# IRRemote.net
KiCad netlist of a schematic drawn in EAGLE
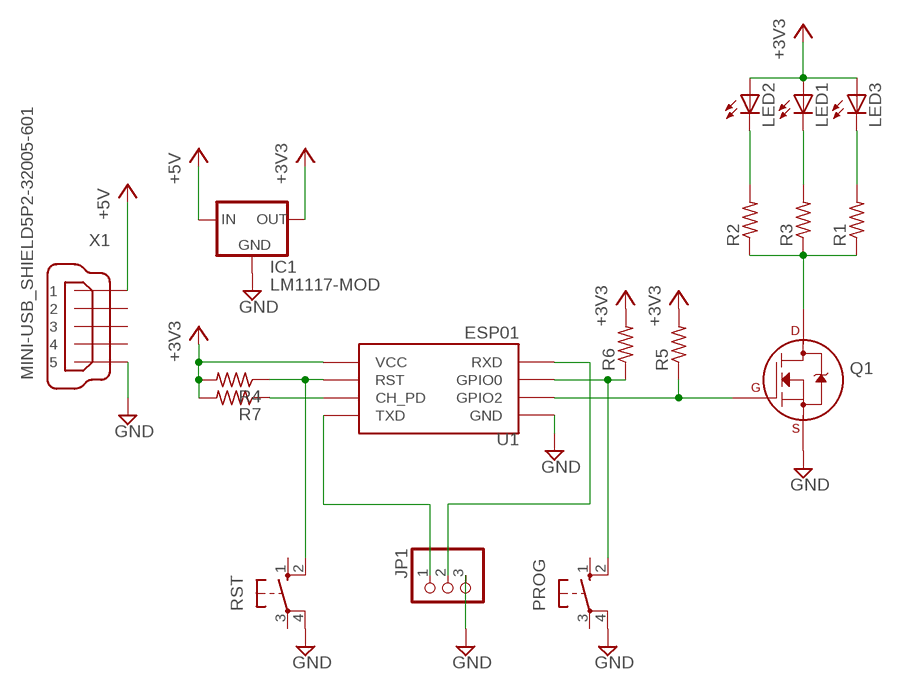
[diagram p0: schematic, sheet 1]

(export (version "E")
  (design (tool "Eeschema 10.0.6"))
  (components
    (comp (ref "IC1")
      (value "LM1117-MOD")
      (footprint "eagle-import:TO220BV")
      (libsource (lib "eagle-import") (part "LM1117-MOD"))
    )
    (comp (ref "JP1")
      (value "PINHD-1X3")
      (footprint "eagle-import:1X03")
      (libsource (lib "eagle-import") (part "PINHD-1X3"))
    )
    (comp (ref "LED1")
      (value "LED5MM")
      (footprint "eagle-import:LED5MM")
      (libsource (lib "eagle-import") (part "LED5MM"))
    )
    (comp (ref "LED2")
      (value "LED5MM")
      (footprint "eagle-import:LED5MM")
      (libsource (lib "eagle-import") (part "LED5MM"))
    )
    (comp (ref "LED3")
      (value "LED5MM")
      (footprint "eagle-import:LED5MM")
      (libsource (lib "eagle-import") (part "LED5MM"))
    )
    (comp (ref "PROG")
      (value "10-XX")
      (footprint "eagle-import:B3F-10XX")
      (fields (field (name "MPN") "B3F-1000"))
      (libsource (lib "eagle-import") (part "10-XX"))
    )
    (comp (ref "Q1")
      (value "2N7000_TO92")
      (footprint "eagle-import:TO-92")
      (libsource (lib "eagle-import") (part "2N700_TO920"))
    )
    (comp (ref "R1")
      (value "R-US_0309/10")
      (footprint "eagle-import:0309_10")
      (libsource (lib "eagle-import") (part "R-US_0309/10"))
    )
    (comp (ref "R2")
      (value "R-US_0309/10")
      (footprint "eagle-import:0309_10")
      (libsource (lib "eagle-import") (part "R-US_0309/10"))
    )
    (comp (ref "R3")
      (value "R-US_0309/10")
      (footprint "eagle-import:0309_10")
      (libsource (lib "eagle-import") (part "R-US_0309/10"))
    )
    (comp (ref "R4")
      (value "R-US_0309/10")
      (footprint "eagle-import:0309_10")
      (libsource (lib "eagle-import") (part "R-US_0309/10"))
    )
    (comp (ref "R5")
      (value "R-US_0309/10")
      (footprint "eagle-import:0309_10")
      (libsource (lib "eagle-import") (part "R-US_0309/10"))
    )
    (comp (ref "R6")
      (value "R-US_0309/10")
      (footprint "eagle-import:0309_10")
      (libsource (lib "eagle-import") (part "R-US_0309/10"))
    )
    (comp (ref "R7")
      (value "R-US_0309/10")
      (footprint "eagle-import:0309_10")
      (libsource (lib "eagle-import") (part "R-US_0309/10"))
    )
    (comp (ref "RST")
      (value "10-XX")
      (footprint "eagle-import:B3F-10XX")
      (fields (field (name "MPN") "B3F-1000"))
      (libsource (lib "eagle-import") (part "10-XX"))
    )
    (comp (ref "U1")
      (value "ESP01")
      (footprint "eagle-import:ESP01A")
      (libsource (lib "eagle-import") (part "ESP01"))
    )
    (comp (ref "X1")
      (value "MINI-USB_SHIELD5P2-32005-601")
      (footprint "eagle-import:32005-601")
      (libsource (lib "eagle-import") (part "MINI-USB_SHIELD5P2-32005-601"))
    )
  )
  (nets
    (net (code "1") (name "+3V3") (class "Default")
      (node (ref "IC1") (pin "2") (pinfunction "VOUT_2") (pintype "bidirectional"))
      (node (ref "LED1") (pin "A") (pinfunction "A_A") (pintype "passive"))
      (node (ref "LED2") (pin "A") (pinfunction "A_A") (pintype "passive"))
      (node (ref "LED3") (pin "A") (pinfunction "A_A") (pintype "passive"))
      (node (ref "R4") (pin "2") (pinfunction "2_2") (pintype "passive"))
      (node (ref "R5") (pin "2") (pinfunction "2_2") (pintype "passive"))
      (node (ref "R6") (pin "2") (pinfunction "2_2") (pintype "passive"))
      (node (ref "R7") (pin "2") (pinfunction "2_2") (pintype "passive"))
      (node (ref "U1") (pin "VCC") (pinfunction "VCC_VCC") (pintype "bidirectional"))
    )
    (net (code "2") (name "+5V") (class "Default")
      (node (ref "IC1") (pin "3") (pinfunction "VIN_3") (pintype "bidirectional"))
      (node (ref "X1") (pin "1") (pinfunction "1_1") (pintype "passive"))
    )
    (net (code "3") (name "GND") (class "Default")
      (node (ref "IC1") (pin "1") (pinfunction "GND_1") (pintype "bidirectional"))
      (node (ref "JP1") (pin "3") (pinfunction "3_3") (pintype "passive"))
      (node (ref "PROG") (pin "4") (pinfunction "P1_4") (pintype "passive"))
      (node (ref "Q1") (pin "1") (pinfunction "S_1") (pintype "bidirectional"))
      (node (ref "RST") (pin "4") (pinfunction "P1_4") (pintype "passive"))
      (node (ref "U1") (pin "GND") (pinfunction "GND_GND") (pintype "bidirectional"))
      (node (ref "X1") (pin "5") (pinfunction "5_5") (pintype "passive"))
    )
    (net (code "4") (name "Net-(LED1-C)") (class "Default")
      (node (ref "LED1") (pin "K") (pinfunction "C_K") (pintype "passive"))
      (node (ref "R3") (pin "2") (pinfunction "2_2") (pintype "passive"))
    )
    (net (code "5") (name "Net-(LED2-C)") (class "Default")
      (node (ref "LED2") (pin "K") (pinfunction "C_K") (pintype "passive"))
      (node (ref "R2") (pin "2") (pinfunction "2_2") (pintype "passive"))
    )
    (net (code "6") (name "Net-(LED3-C)") (class "Default")
      (node (ref "LED3") (pin "K") (pinfunction "C_K") (pintype "passive"))
      (node (ref "R1") (pin "2") (pinfunction "2_2") (pintype "passive"))
    )
    (net (code "7") (name "Net-(PROG-S1)") (class "Default")
      (node (ref "PROG") (pin "2") (pinfunction "S1_2") (pintype "passive"))
      (node (ref "R6") (pin "1") (pinfunction "1_1") (pintype "passive"))
      (node (ref "U1") (pin "GPIO0") (pinfunction "GPIO0_GPIO0") (pintype "bidirectional"))
    )
    (net (code "8") (name "Net-(Q1-D)") (class "Default")
      (node (ref "Q1") (pin "3") (pinfunction "D_3") (pintype "bidirectional"))
      (node (ref "R1") (pin "1") (pinfunction "1_1") (pintype "passive"))
      (node (ref "R2") (pin "1") (pinfunction "1_1") (pintype "passive"))
      (node (ref "R3") (pin "1") (pinfunction "1_1") (pintype "passive"))
    )
    (net (code "9") (name "Net-(Q1-G)") (class "Default")
      (node (ref "Q1") (pin "2") (pinfunction "G_2") (pintype "tri_state"))
      (node (ref "R5") (pin "1") (pinfunction "1_1") (pintype "passive"))
      (node (ref "U1") (pin "GPIO2") (pinfunction "GPIO2_GPIO2") (pintype "bidirectional"))
    )
    (net (code "10") (name "Net-(R7-Pad1)") (class "Default")
      (node (ref "R7") (pin "1") (pinfunction "1_1") (pintype "passive"))
      (node (ref "U1") (pin "CH_PD") (pinfunction "CH_PD_CH_PD") (pintype "bidirectional"))
    )
    (net (code "11") (name "Net-(RST-S1)") (class "Default")
      (node (ref "R4") (pin "1") (pinfunction "1_1") (pintype "passive"))
      (node (ref "RST") (pin "2") (pinfunction "S1_2") (pintype "passive"))
      (node (ref "U1") (pin "RST") (pinfunction "RST_RST") (pintype "bidirectional"))
    )
    (net (code "12") (name "Net-(U1-RXD)") (class "Default")
      (node (ref "JP1") (pin "2") (pinfunction "2_2") (pintype "passive"))
      (node (ref "U1") (pin "RX") (pinfunction "RXD_RX") (pintype "bidirectional"))
    )
    (net (code "13") (name "Net-(U1-TXD)") (class "Default")
      (node (ref "JP1") (pin "1") (pinfunction "1_1") (pintype "passive"))
      (node (ref "U1") (pin "TX") (pinfunction "TXD_TX") (pintype "bidirectional"))
    )
    (net (code "14") (name "unconnected-(PROG-P-Pad3)") (class "Default")
      (node (ref "PROG") (pin "3") (pinfunction "P_3") (pintype "passive"))
    )
    (net (code "15") (name "unconnected-(PROG-S-Pad1)") (class "Default")
      (node (ref "PROG") (pin "1") (pinfunction "S_1") (pintype "passive"))
    )
    (net (code "16") (name "unconnected-(RST-P-Pad3)") (class "Default")
      (node (ref "RST") (pin "3") (pinfunction "P_3") (pintype "passive"))
    )
    (net (code "17") (name "unconnected-(RST-S-Pad1)") (class "Default")
      (node (ref "RST") (pin "1") (pinfunction "S_1") (pintype "passive"))
    )
    (net (code "18") (name "unconnected-(X1-Pad2)") (class "Default")
      (node (ref "X1") (pin "2") (pinfunction "2_2") (pintype "passive"))
    )
    (net (code "19") (name "unconnected-(X1-Pad3)") (class "Default")
      (node (ref "X1") (pin "3") (pinfunction "3_3") (pintype "passive"))
    )
    (net (code "20") (name "unconnected-(X1-Pad4)") (class "Default")
      (node (ref "X1") (pin "4") (pinfunction "4_4") (pintype "passive"))
    )
  )
)
